# RADC-Peripherals-S05-V00.net
KiCad netlist of a schematic drawn in Altium Designer
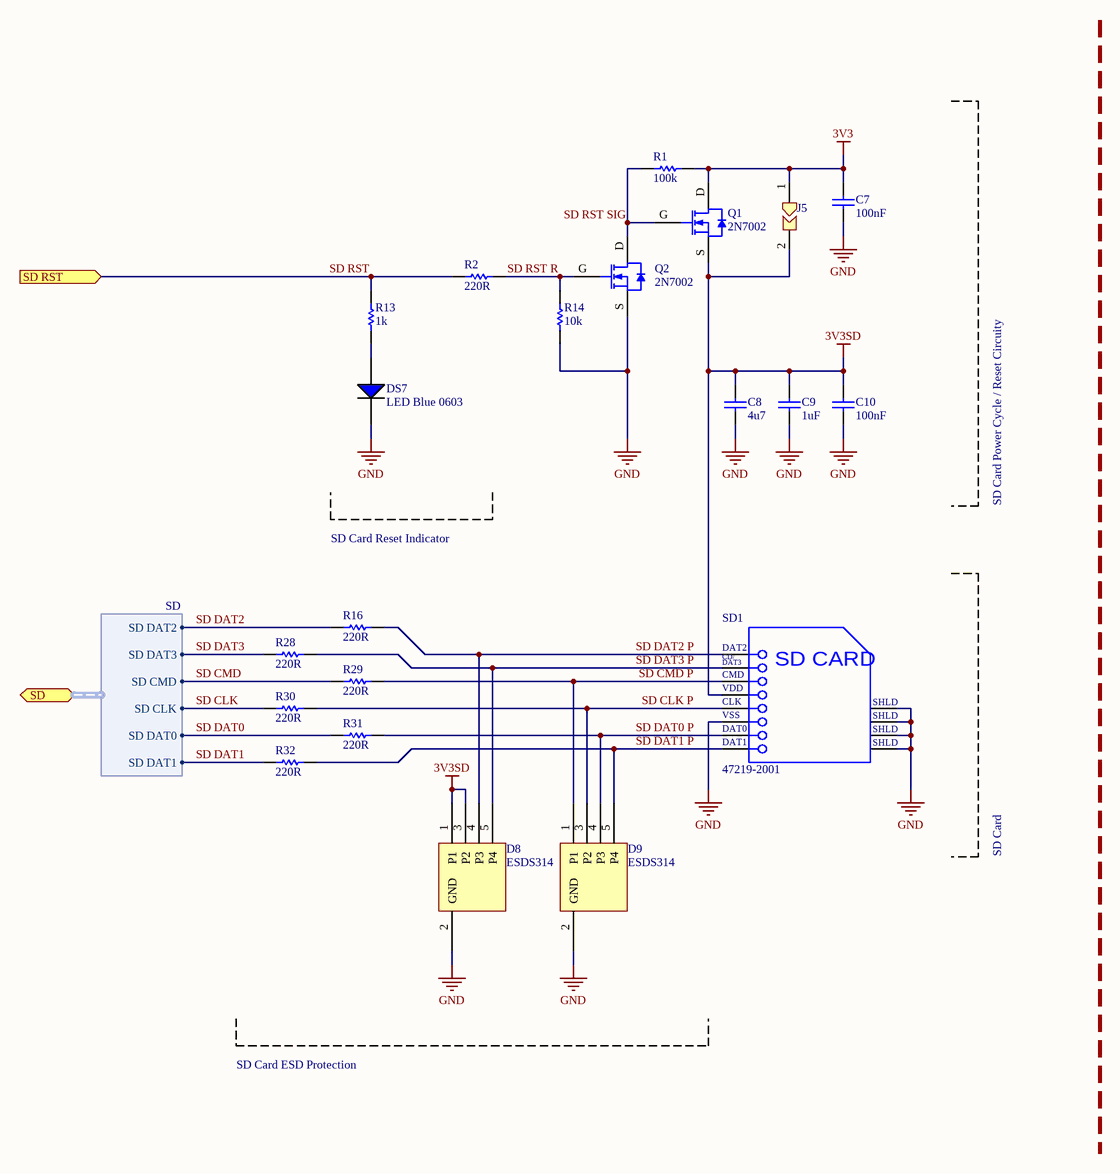
[diagram p0: RADC-Peripherals-S05-V00.SchDoc]

(export (version "E")
  (design (tool "Eeschema 10.0.6"))
  (components
    (comp (ref "C7")
      (value "100nF")
      (footprint "Cap_Ceramic_0603")
      (description "Capacitor, Ceramic, SMD, 100nF, 50V, 5%, X7R, 0603")
      (libsource (lib "StandardCapacitors") (part "100nF 50V 5% X7R 0603"))
    )
    (comp (ref "C8")
      (value "4u7")
      (footprint "Cap_Ceramic_0603")
      (description "Capacitor, Ceramic, SMD, 4u7, 50V, 5%, X7R, 0603")
      (libsource (lib "StandardCapacitors") (part "4u7 50V 5% X7R 0603"))
    )
    (comp (ref "C9")
      (value "1uF")
      (footprint "Cap_Ceramic_0603")
      (description "Capacitor, Ceramic, SMD, 1uF, 25V, 5%, X7R, 0603")
      (libsource (lib "StandardCapacitors") (part "1uF 25V 5% X7R 0603"))
    )
    (comp (ref "C10")
      (value "100nF")
      (footprint "Cap_Ceramic_0603")
      (description "Capacitor, Ceramic, SMD, 100nF, 50V, 5%, X7R, 0603")
      (libsource (lib "StandardCapacitors") (part "100nF 50V 5% X7R 0603"))
    )
    (comp (ref "D8")
      (value "ESDS314")
      (footprint "SOT-23-5")
      (description "6.5V (Typ) Clamp 25A (8/20µs) Ipp Tvs Diode Surface Mount SOT-23-5")
      (libsource (lib "QUTMS_DiodeLibrary") (part "ESDS314"))
    )
    (comp (ref "D9")
      (value "ESDS314")
      (footprint "SOT-23-5")
      (description "6.5V (Typ) Clamp 25A (8/20µs) Ipp Tvs Diode Surface Mount SOT-23-5")
      (libsource (lib "QUTMS_DiodeLibrary") (part "ESDS314"))
    )
    (comp (ref "DS7")
      (value "LED Blue 0603")
      (footprint "LED BLUE 0603")
      (libsource (lib "QUTMS_LEDLibrary") (part "LED Blue 0603"))
    )
    (comp (ref "J5")
      (value "Jumper 2Way Solderable")
      (footprint "Jumper_2Way_Solderable")
      (description "Jumper 2Way Vert Solderable")
      (libsource (lib "QUTMS_JumperLibrary") (part "Jumper 2Way Vert Solderable"))
    )
    (comp (ref "Q1")
      (value "2N7002")
      (footprint "SOT23-3")
      (libsource (lib "QUTMS_MOSFETLibrary") (part "2N7002"))
    )
    (comp (ref "Q2")
      (value "2N7002")
      (footprint "SOT23-3")
      (libsource (lib "QUTMS_MOSFETLibrary") (part "2N7002"))
    )
    (comp (ref "R1")
      (value "100k")
      (footprint "Res_ThinFilm_0603")
      (description "Resistor, SMD, 100k, 0.1W, 5%, 0603")
      (libsource (lib "StandardResistors") (part "100k 5%, 0603"))
    )
    (comp (ref "R2")
      (value "220R")
      (footprint "Res_ThinFilm_0603")
      (description "Resistor, SMD, 220R, 0.1W, 5%, 0603")
      (libsource (lib "StandardResistors") (part "220R 5% 0603"))
    )
    (comp (ref "R13")
      (value "1k")
      (footprint "Res_ThinFilm_0603")
      (description "Resistor, SMD, 1k, 0.1W, 5%, 0603")
      (libsource (lib "StandardResistors") (part "1k 5% 0603"))
    )
    (comp (ref "R14")
      (value "10k")
      (footprint "Res_ThinFilm_0603")
      (description "Resistor, SMD, 10k, 0.1W, 5%, 0603")
      (libsource (lib "StandardResistors") (part "10k 5% 0603"))
    )
    (comp (ref "R16")
      (value "220R")
      (footprint "Res_ThinFilm_0603")
      (description "Resistor, SMD, 220R, 0.1W, 5%, 0603")
      (libsource (lib "StandardResistors") (part "220R 5% 0603"))
    )
    (comp (ref "R28")
      (value "220R")
      (footprint "Res_ThinFilm_0603")
      (description "Resistor, SMD, 220R, 0.1W, 5%, 0603")
      (libsource (lib "StandardResistors") (part "220R 5% 0603"))
    )
    (comp (ref "R29")
      (value "220R")
      (footprint "Res_ThinFilm_0603")
      (description "Resistor, SMD, 220R, 0.1W, 5%, 0603")
      (libsource (lib "StandardResistors") (part "220R 5% 0603"))
    )
    (comp (ref "R30")
      (value "220R")
      (footprint "Res_ThinFilm_0603")
      (description "Resistor, SMD, 220R, 0.1W, 5%, 0603")
      (libsource (lib "StandardResistors") (part "220R 5% 0603"))
    )
    (comp (ref "R31")
      (value "220R")
      (footprint "Res_ThinFilm_0603")
      (description "Resistor, SMD, 220R, 0.1W, 5%, 0603")
      (libsource (lib "StandardResistors") (part "220R 5% 0603"))
    )
    (comp (ref "R32")
      (value "220R")
      (footprint "Res_ThinFilm_0603")
      (description "Resistor, SMD, 220R, 0.1W, 5%, 0603")
      (libsource (lib "StandardResistors") (part "220R 5% 0603"))
    )
    (comp (ref "SD1")
      (value "47219-2001")
      (footprint "47219-2001")
      (description "MicroSD Card Connector, Hinge Type, -40 to 85 degC, 8-Pin SMD, RoHS, Tape and Reel")
      (libsource (lib "QUTMS_PeripheralConnectivity") (part "47219-2001"))
    )
  )
  (nets
    (net (code "2") (name "/SD CLK") (class "Default")
      (node (ref "R30") (pin "1") (pinfunction "1_1") (pintype "passive"))
    )
    (net (code "3") (name "/SD CLK P") (class "Default")
      (node (ref "D9") (pin "3") (pinfunction "P2_3") (pintype "passive"))
      (node (ref "R30") (pin "2") (pinfunction "2_2") (pintype "passive"))
      (node (ref "SD1") (pin "5") (pinfunction "CLK_5") (pintype "passive"))
    )
    (net (code "4") (name "/SD CMD") (class "Default")
      (node (ref "R29") (pin "1") (pinfunction "1_1") (pintype "passive"))
    )
    (net (code "5") (name "/SD CMD P") (class "Default")
      (node (ref "D9") (pin "1") (pinfunction "P1_1") (pintype "passive"))
      (node (ref "R29") (pin "2") (pinfunction "2_2") (pintype "passive"))
      (node (ref "SD1") (pin "3") (pinfunction "CMD_3") (pintype "passive"))
    )
    (net (code "6") (name "/SD DAT0") (class "Default")
      (node (ref "R31") (pin "1") (pinfunction "1_1") (pintype "passive"))
    )
    (net (code "7") (name "/SD DAT0 P") (class "Default")
      (node (ref "D9") (pin "4") (pinfunction "P3_4") (pintype "passive"))
      (node (ref "R31") (pin "2") (pinfunction "2_2") (pintype "passive"))
      (node (ref "SD1") (pin "7") (pinfunction "DAT0_7") (pintype "passive"))
    )
    (net (code "8") (name "/SD DAT1") (class "Default")
      (node (ref "R32") (pin "1") (pinfunction "1_1") (pintype "passive"))
    )
    (net (code "9") (name "/SD DAT1 P") (class "Default")
      (node (ref "D9") (pin "5") (pinfunction "P4_5") (pintype "passive"))
      (node (ref "R32") (pin "2") (pinfunction "2_2") (pintype "passive"))
      (node (ref "SD1") (pin "8") (pinfunction "DAT1_8") (pintype "passive"))
    )
    (net (code "10") (name "/SD DAT2") (class "Default")
      (node (ref "R16") (pin "1") (pinfunction "1_1") (pintype "passive"))
    )
    (net (code "11") (name "/SD DAT2 P") (class "Default")
      (node (ref "D8") (pin "4") (pinfunction "P3_4") (pintype "passive"))
      (node (ref "R16") (pin "2") (pinfunction "2_2") (pintype "passive"))
      (node (ref "SD1") (pin "1") (pinfunction "DAT2_1") (pintype "passive"))
    )
    (net (code "12") (name "/SD DAT3") (class "Default")
      (node (ref "R28") (pin "1") (pinfunction "1_1") (pintype "passive"))
    )
    (net (code "13") (name "/SD DAT3 P") (class "Default")
      (node (ref "D8") (pin "5") (pinfunction "P4_5") (pintype "passive"))
      (node (ref "R28") (pin "2") (pinfunction "2_2") (pintype "passive"))
      (node (ref "SD1") (pin "2") (pinfunction "CD/DAT3_2") (pintype "passive"))
    )
    (net (code "14") (name "/SD RST") (class "Default")
      (node (ref "R13") (pin "2") (pinfunction "2_2") (pintype "passive"))
      (node (ref "R2") (pin "1") (pinfunction "1_1") (pintype "passive"))
    )
    (net (code "15") (name "/SD RST R") (class "Default")
      (node (ref "Q2") (pin "G") (pinfunction "G_G") (pintype "passive"))
      (node (ref "R14") (pin "2") (pinfunction "2_2") (pintype "passive"))
      (node (ref "R2") (pin "2") (pinfunction "2_2") (pintype "passive"))
    )
    (net (code "16") (name "/SD RST SIG") (class "Default")
      (node (ref "Q1") (pin "G") (pinfunction "G_G") (pintype "passive"))
      (node (ref "Q2") (pin "D") (pinfunction "D_D") (pintype "passive"))
      (node (ref "R1") (pin "2") (pinfunction "2_2") (pintype "passive"))
    )
    (net (code "18") (name "3V3") (class "Default")
      (node (ref "C7") (pin "2") (pinfunction "2_2") (pintype "passive"))
      (node (ref "J5") (pin "1") (pinfunction "1_1") (pintype "passive"))
      (node (ref "Q1") (pin "D") (pinfunction "D_D") (pintype "passive"))
      (node (ref "R1") (pin "1") (pinfunction "1_1") (pintype "passive"))
    )
    (net (code "19") (name "3V3SD") (class "Default")
      (node (ref "C10") (pin "2") (pinfunction "2_2") (pintype "passive"))
      (node (ref "C8") (pin "2") (pinfunction "2_2") (pintype "passive"))
      (node (ref "C9") (pin "2") (pinfunction "2_2") (pintype "passive"))
      (node (ref "D8") (pin "1") (pinfunction "P1_1") (pintype "passive"))
      (node (ref "D8") (pin "3") (pinfunction "P2_3") (pintype "passive"))
      (node (ref "J5") (pin "2") (pinfunction "2_2") (pintype "passive"))
      (node (ref "Q1") (pin "S") (pinfunction "S_S") (pintype "passive"))
      (node (ref "SD1") (pin "4") (pinfunction "VDD_4") (pintype "passive"))
    )
    (net (code "20") (name "GND") (class "Default")
      (node (ref "C10") (pin "1") (pinfunction "1_1") (pintype "passive"))
      (node (ref "C7") (pin "1") (pinfunction "1_1") (pintype "passive"))
      (node (ref "C8") (pin "1") (pinfunction "1_1") (pintype "passive"))
      (node (ref "C9") (pin "1") (pinfunction "1_1") (pintype "passive"))
      (node (ref "D8") (pin "2") (pinfunction "GND_2") (pintype "passive"))
      (node (ref "D9") (pin "2") (pinfunction "GND_2") (pintype "passive"))
      (node (ref "DS7") (pin "2") (pinfunction "C_2") (pintype "passive"))
      (node (ref "Q2") (pin "S") (pinfunction "S_S") (pintype "passive"))
      (node (ref "R14") (pin "1") (pinfunction "1_1") (pintype "passive"))
      (node (ref "SD1") (pin "10") (pinfunction "SHLD_10") (pintype "passive"))
      (node (ref "SD1") (pin "11") (pinfunction "SHLD_11") (pintype "passive"))
      (node (ref "SD1") (pin "12") (pinfunction "SHLD_12") (pintype "passive"))
      (node (ref "SD1") (pin "6") (pinfunction "VSS_6") (pintype "passive"))
      (node (ref "SD1") (pin "9") (pinfunction "SHLD_9") (pintype "passive"))
    )
    (net (code "21") (name "Net-(DS7-A)") (class "Default")
      (node (ref "DS7") (pin "1") (pinfunction "A_1") (pintype "passive"))
      (node (ref "R13") (pin "1") (pinfunction "1_1") (pintype "passive"))
    )
  )
)
